# PPS_IN.net
KiCad netlist of a schematic drawn in Altium Designer
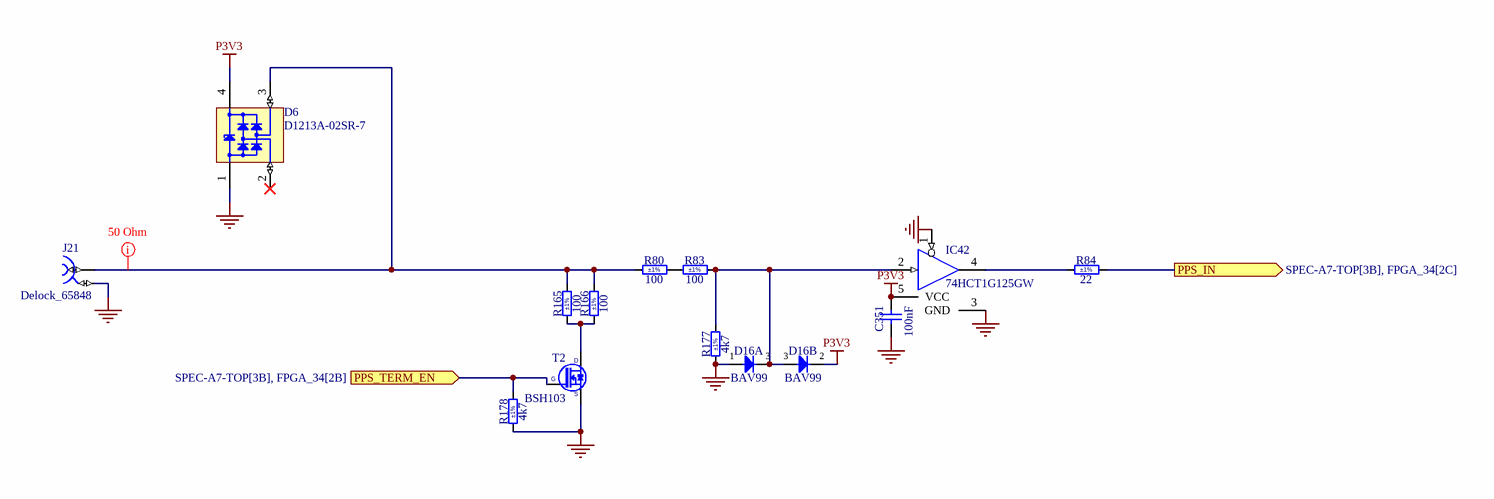
[diagram p0: PPS_IN.SchDoc]

(export (version "E")
  (design (tool "Eeschema 10.0.6"))
  (components
    (comp (ref "C351")
      (value "100nF")
      (footprint "CAPC0603X33N")
      (description "Non-polarised capacitor")
      (fields
        (field (name "PART NUMBER") "CC0201_100NF_6.3V_10%_X5R")
        (field (name "VOLTAGE") "6.3V")
        (field (name "AUTHOR") "CERN DEM JLC")
      )
      (libsource (lib "Capacitors") (part "Capacitor - non polarized"))
    )
    (comp (ref "D6")
      (value "D1213A-02SR-7")
      (footprint "SOT190P238X100-4N")
      (description "D1213A-02SR Series 400 mW Uni-Directional Surface Mount TVS Diode - SOT-143")
      (libsource (lib "TechnoSystem Workspace") (part "D1213A-02SR-7"))
    )
    (comp (ref "D16")
      (value "BAV99")
      (footprint "SOT95P240X110-3N")
      (description "Serial Diode")
      (fields
        (field (name "VOLTAGE") "70V")
        (field (name "POWER") "350mW")
        (field (name "AUTHOR") "CERN DEM JLC")
      )
      (libsource (lib "ICs And Semiconductors") (part "Diode x2 A1C3_A3C2"))
    )
    (comp (ref "IC42")
      (value "74HCT1G125GW")
      (footprint "SOT65P210X110-5N")
      (description "Single Bus Buffer Gate With 3-State Output")
      (fields (field (name "MANUFACTURER") "NEXPERIA") (field (name "AUTHOR") "CERN DEM JMW"))
      (libsource (lib "ICs And Semiconductors") (part "741G125"))
    )
    (comp (ref "J21")
      (value "Delock_65848")
      (footprint "Delock_65848")
      (description "SMA connector Delock 65848")
      (libsource (lib "TechnoSystem Workspace") (part "Coax_1Female_1Shield"))
    )
    (comp (ref "R80")
      (value "100")
      (footprint "RESC1005X40N")
      (description "Resistor - 1%")
      (fields
        (field (name "TOLERANCE") "±1%")
        (field (name "PART NUMBER") "R0402_100R_1%_0.0625W_100PPM")
        (field (name "POWER") "0.0625W")
        (field (name "AUTHOR") "CERN DEM JLC")
      )
      (libsource (lib "Resistors") (part "Resistor - 1%"))
    )
    (comp (ref "R83")
      (value "100")
      (footprint "RESC1005X40N")
      (description "Resistor - 1%")
      (fields
        (field (name "TOLERANCE") "±1%")
        (field (name "PART NUMBER") "R0402_100R_1%_0.0625W_100PPM")
        (field (name "POWER") "0.0625W")
        (field (name "AUTHOR") "CERN DEM JLC")
      )
      (libsource (lib "Resistors") (part "Resistor - 1%"))
    )
    (comp (ref "R84")
      (value "22")
      (footprint "RESC1005X40N")
      (description "Resistor - 1%")
      (fields
        (field (name "TOLERANCE") "±1%")
        (field (name "PART NUMBER") "R0402_22R_1%_0.0625W_100PPM")
        (field (name "POWER") "0.0625W")
        (field (name "AUTHOR") "CERN DEM JLC")
      )
      (libsource (lib "Resistors") (part "Resistor - 1%"))
    )
    (comp (ref "R165")
      (value "100")
      (footprint "RESC1005X40N")
      (description "Resistor - 1%")
      (fields
        (field (name "TOLERANCE") "±1%")
        (field (name "PART NUMBER") "R0402_100R_1%_0.0625W_100PPM")
        (field (name "POWER") "0.0625W")
        (field (name "AUTHOR") "CERN DEM JLC")
      )
      (libsource (lib "Resistors") (part "Resistor - 1%"))
    )
    (comp (ref "R166")
      (value "100")
      (footprint "RESC1005X40N")
      (description "Resistor - 1%")
      (fields
        (field (name "TOLERANCE") "±1%")
        (field (name "PART NUMBER") "R0402_100R_1%_0.0625W_100PPM")
        (field (name "POWER") "0.0625W")
        (field (name "AUTHOR") "CERN DEM JLC")
      )
      (libsource (lib "Resistors") (part "Resistor - 1%"))
    )
    (comp (ref "R177")
      (value "4k7")
      (footprint "RESC1005X40N")
      (description "Resistor - 1%")
      (fields
        (field (name "TOLERANCE") "±1%")
        (field (name "PART NUMBER") "R0402_4K7_1%_0.0625W_100PPM")
        (field (name "POWER") "0.0625W")
        (field (name "AUTHOR") "CERN DEM JLC")
      )
      (libsource (lib "Resistors") (part "Resistor - 1%"))
    )
    (comp (ref "R178")
      (value "4k7")
      (footprint "RESC1005X40N")
      (description "Resistor - 1%")
      (fields
        (field (name "TOLERANCE") "±1%")
        (field (name "PART NUMBER") "R0402_4K7_1%_0.0625W_100PPM")
        (field (name "POWER") "0.0625W")
        (field (name "AUTHOR") "CERN DEM JLC")
      )
      (libsource (lib "Resistors") (part "Resistor - 1%"))
    )
    (comp (ref "T2")
      (value "BSH103")
      (footprint "SOT95P230X110-3N")
      (description "N-CHANNEL MOSFET WITH DIODE")
      (fields (field (name "MANUFACTURER") "NEXPERIA") (field (name "AUTHOR") "CERN DEM JLC"))
      (libsource (lib "ICs And Semiconductors") (part "N-MOSFET-D 1G 2S 3D"))
    )
  )
  (nets
    (net (code "1") (name "/PPS_IN") (class "Default")
      (node (ref "R84") (pin "2") (pinfunction "2_2") (pintype "passive"))
    )
    (net (code "2") (name "/PPS_TERM_EN") (class "Default")
      (node (ref "R178") (pin "2") (pinfunction "2_2") (pintype "passive"))
      (node (ref "T2") (pin "1") (pinfunction "G_1") (pintype "passive"))
    )
    (net (code "3") (name "GND") (class "Default")
      (node (ref "C351") (pin "1") (pinfunction "1_1") (pintype "passive"))
      (node (ref "D16") (pin "1") (pinfunction "A_1") (pintype "passive"))
      (node (ref "D6") (pin "1") (pinfunction "GND_1") (pintype "power_in"))
      (node (ref "IC42") (pin "1") (pinfunction "~{G}_1") (pintype "input"))
      (node (ref "IC42") (pin "3") (pinfunction "GND_3") (pintype "power_in"))
      (node (ref "J21") (pin "2") (pinfunction "2_2") (pintype "bidirectional"))
      (node (ref "R177") (pin "1") (pinfunction "1_1") (pintype "passive"))
      (node (ref "R178") (pin "1") (pinfunction "1_1") (pintype "passive"))
      (node (ref "T2") (pin "2") (pinfunction "S_2") (pintype "passive"))
    )
    (net (code "4") (name "Net-(D6-I{slash}O2)") (class "Default")
      (node (ref "D6") (pin "3") (pinfunction "I/O2_3") (pintype "bidirectional"))
      (node (ref "J21") (pin "1") (pinfunction "1_1") (pintype "bidirectional"))
      (node (ref "R165") (pin "2") (pinfunction "2_2") (pintype "passive"))
      (node (ref "R166") (pin "2") (pinfunction "2_2") (pintype "passive"))
      (node (ref "R80") (pin "1") (pinfunction "1_1") (pintype "passive"))
    )
    (net (code "5") (name "Net-(D16A-COMAC)") (class "Default")
      (node (ref "D16") (pin "3") (pinfunction "COMAC_3") (pintype "passive"))
      (node (ref "IC42") (pin "2") (pinfunction "IN_2") (pintype "input"))
      (node (ref "R177") (pin "2") (pinfunction "2_2") (pintype "passive"))
      (node (ref "R83") (pin "2") (pinfunction "2_2") (pintype "passive"))
    )
    (net (code "6") (name "Net-(IC42-OUT)") (class "Default")
      (node (ref "IC42") (pin "4") (pinfunction "OUT_4") (pintype "tri_state"))
      (node (ref "R84") (pin "1") (pinfunction "1_1") (pintype "passive"))
    )
    (net (code "7") (name "Net-(R80-Pad2)") (class "Default")
      (node (ref "R80") (pin "2") (pinfunction "2_2") (pintype "passive"))
      (node (ref "R83") (pin "1") (pinfunction "1_1") (pintype "passive"))
    )
    (net (code "8") (name "Net-(T2-D)") (class "Default")
      (node (ref "R165") (pin "1") (pinfunction "1_1") (pintype "passive"))
      (node (ref "R166") (pin "1") (pinfunction "1_1") (pintype "passive"))
      (node (ref "T2") (pin "3") (pinfunction "D_3") (pintype "passive"))
    )
    (net (code "9") (name "P3V3") (class "Default")
      (node (ref "C351") (pin "2") (pinfunction "2_2") (pintype "passive"))
      (node (ref "D16") (pin "2") (pinfunction "C_2") (pintype "passive"))
      (node (ref "D6") (pin "4") (pinfunction "VCC_4") (pintype "power_in"))
      (node (ref "IC42") (pin "5") (pinfunction "VCC_5") (pintype "power_in"))
    )
    (net (code "10") (name "unconnected-(D6-I{slash}O1-Pad2)") (class "Default")
      (node (ref "D6") (pin "2") (pinfunction "I/O1_2") (pintype "bidirectional+no_connect"))
    )
  )
)
